# ROS_Car_F4VG_2024-01-24.net
KiCad netlist of a schematic drawn in EasyEDA Pro
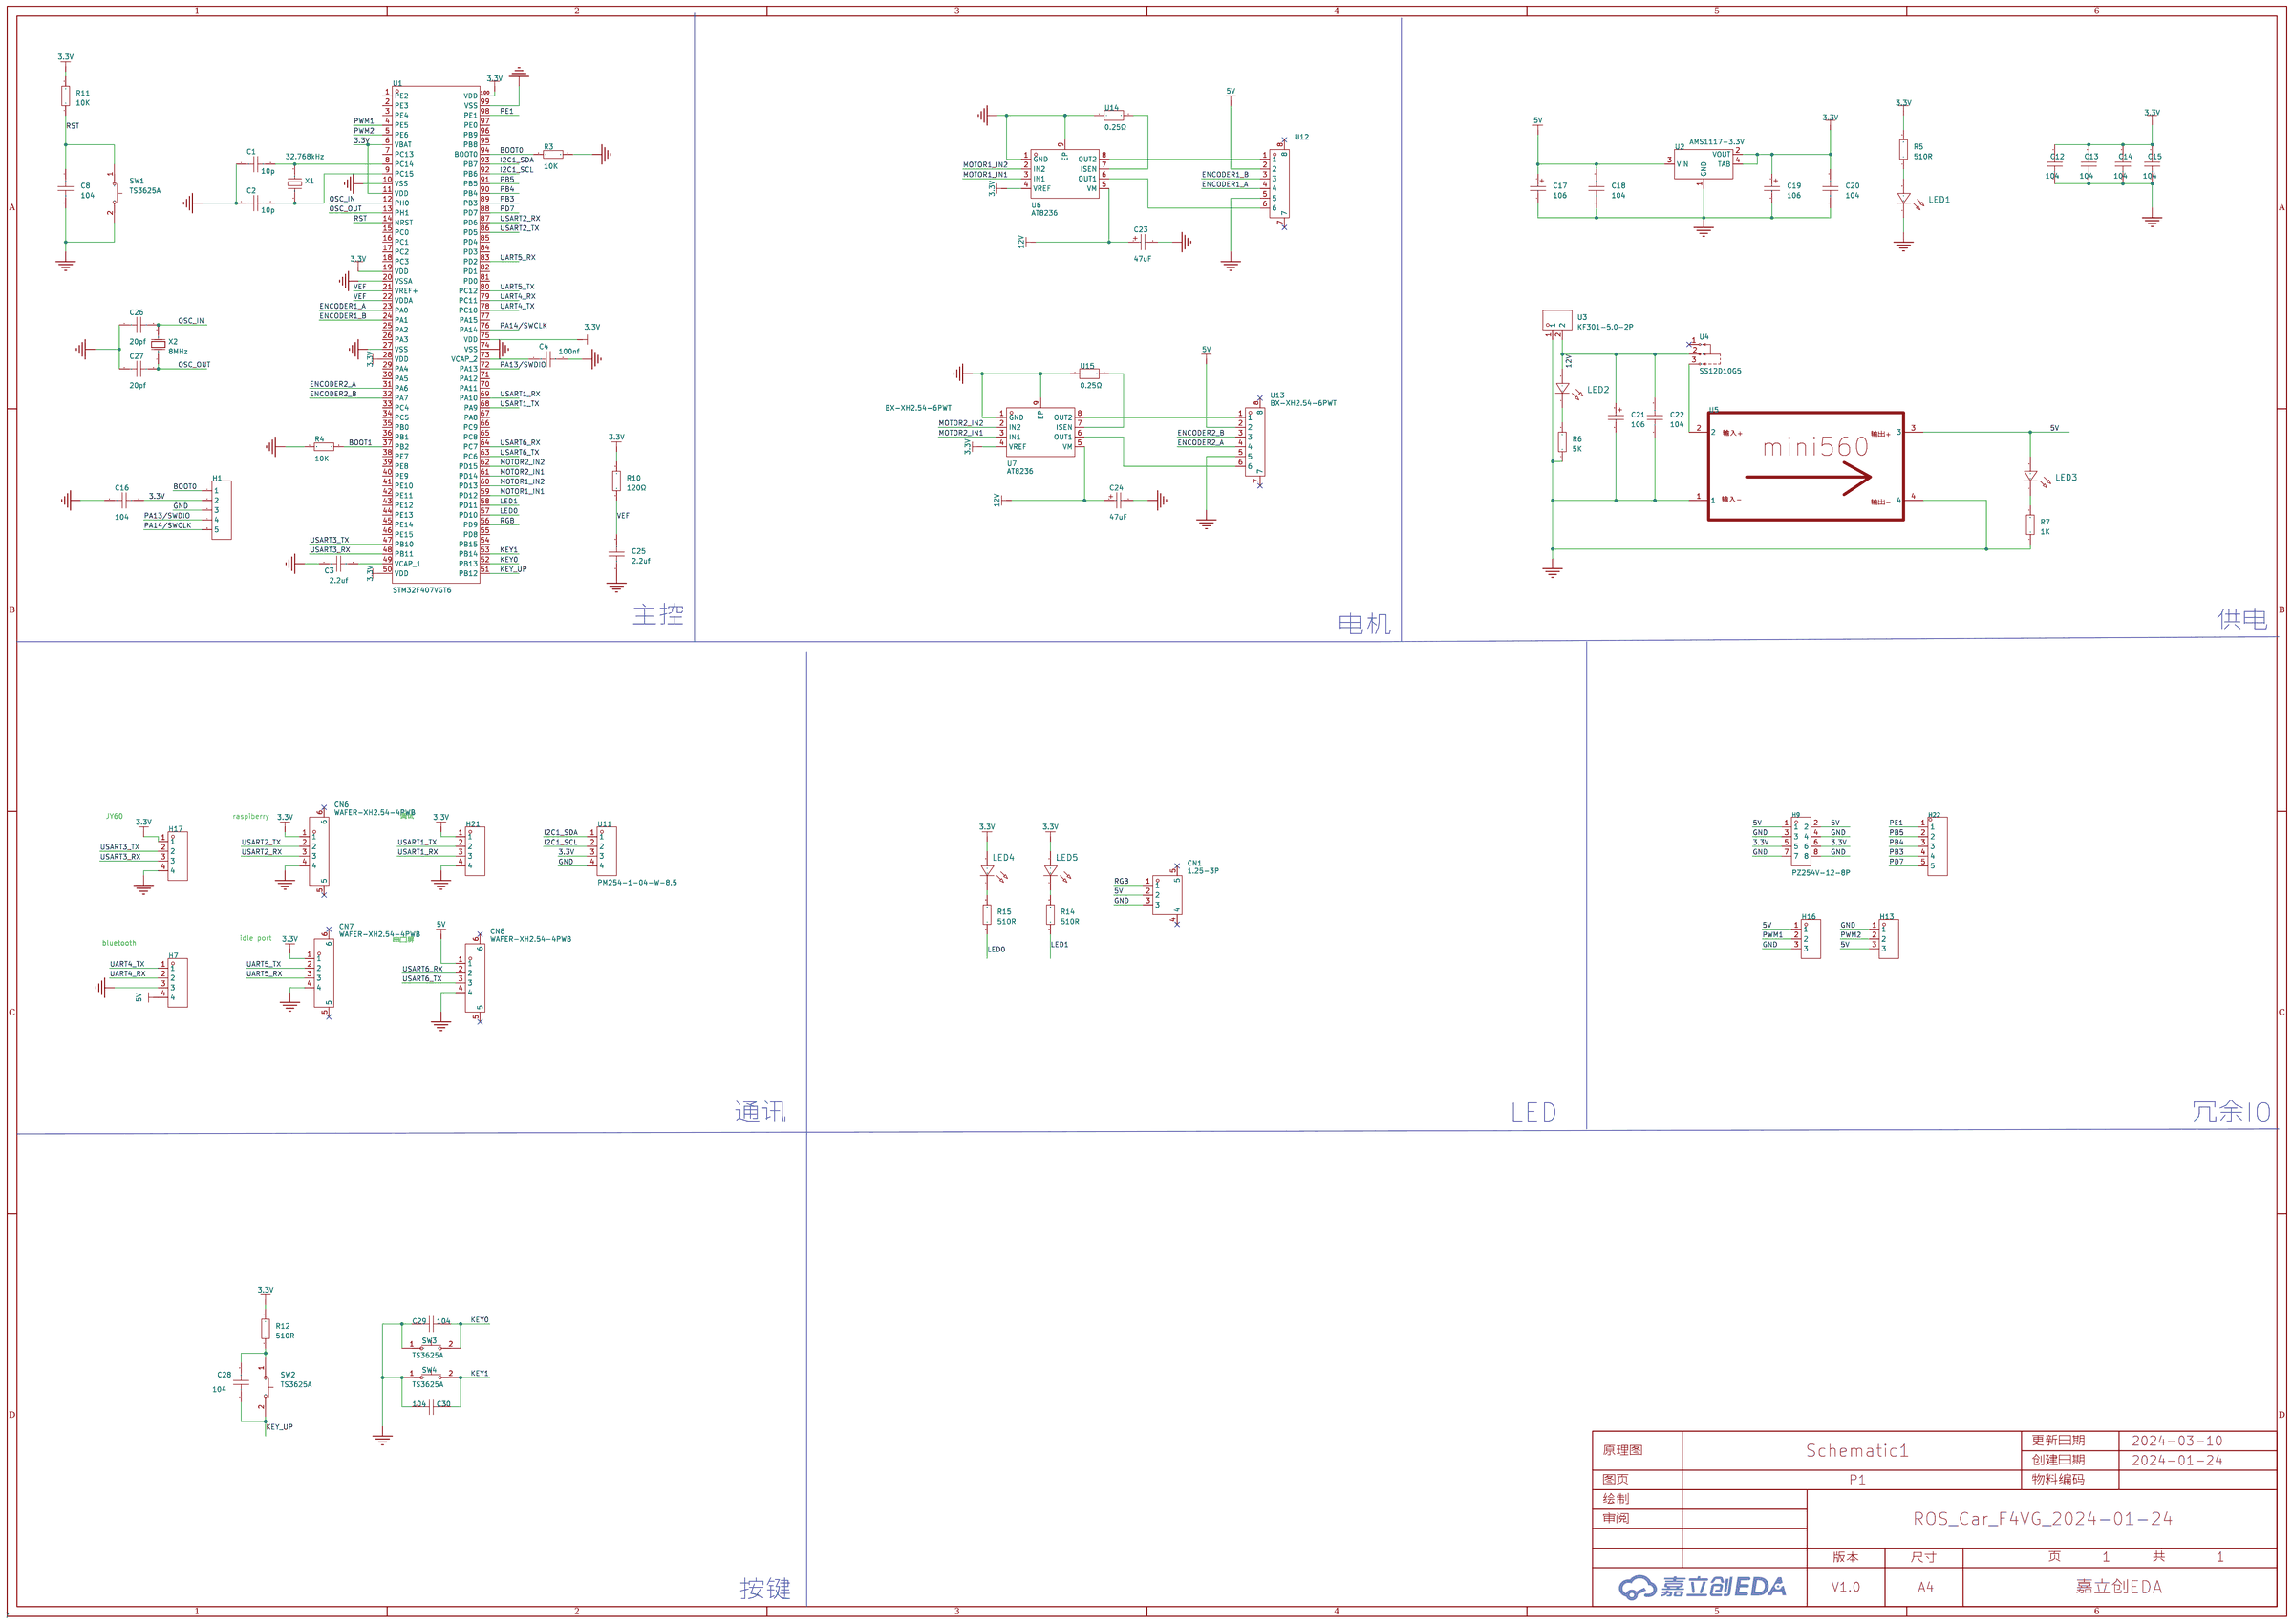
[diagram p0: schematic sheet]

(export (version "E")
  (design (tool "Eeschema 10.0.6"))
  (components
    (comp (ref "C1")
      (value "10p")
      (footprint "easyedapro:C0603")
      (libsource (lib "easyedapro") (part "CapAcitance"))
    )
    (comp (ref "C2")
      (value "10p")
      (footprint "easyedapro:C0603")
      (libsource (lib "easyedapro") (part "CapAcitance"))
    )
    (comp (ref "C3")
      (value "2.2uf")
      (footprint "easyedapro:C0603")
      (libsource (lib "easyedapro") (part "CapAcitance"))
    )
    (comp (ref "C4")
      (value "100nf")
      (footprint "easyedapro:C0603")
      (libsource (lib "easyedapro") (part "CapAcitance"))
    )
    (comp (ref "C8")
      (value "104")
      (footprint "easyedapro:C0603")
      (libsource (lib "easyedapro") (part "CapAcitance"))
    )
    (comp (ref "C12")
      (value "104")
      (footprint "easyedapro:C0603")
      (libsource (lib "easyedapro") (part "CapAcitance"))
    )
    (comp (ref "C13")
      (value "104")
      (footprint "easyedapro:C0603")
      (libsource (lib "easyedapro") (part "CapAcitance"))
    )
    (comp (ref "C14")
      (value "104")
      (footprint "easyedapro:C0603")
      (libsource (lib "easyedapro") (part "CapAcitance"))
    )
    (comp (ref "C15")
      (value "104")
      (footprint "easyedapro:C0603")
      (libsource (lib "easyedapro") (part "CapAcitance"))
    )
    (comp (ref "C16")
      (value "104")
      (footprint "easyedapro:C0603")
      (libsource (lib "easyedapro") (part "CapAcitance"))
    )
    (comp (ref "C17")
      (value "106")
      (footprint "easyedapro:C_Ele_SMD_4x5.5mm")
      (libsource (lib "easyedapro") (part "CAP"))
    )
    (comp (ref "C18")
      (value "104")
      (footprint "easyedapro:C0603")
      (libsource (lib "easyedapro") (part "CapAcitance"))
    )
    (comp (ref "C19")
      (value "106")
      (footprint "easyedapro:C_Ele_SMD_4x5.5mm")
      (libsource (lib "easyedapro") (part "CAP"))
    )
    (comp (ref "C20")
      (value "104")
      (footprint "easyedapro:C0603")
      (libsource (lib "easyedapro") (part "CapAcitance"))
    )
    (comp (ref "C21")
      (value "106")
      (footprint "easyedapro:C_Ele_SMD_4x5.5mm")
      (libsource (lib "easyedapro") (part "CAP"))
    )
    (comp (ref "C22")
      (value "104")
      (footprint "easyedapro:C0603")
      (libsource (lib "easyedapro") (part "CapAcitance"))
    )
    (comp (ref "C23")
      (value "47uF")
      (footprint "easyedapro:C_Ele_SMD_4x5.5mm")
      (libsource (lib "easyedapro") (part "CAP"))
    )
    (comp (ref "C24")
      (value "47uF")
      (footprint "easyedapro:C_Ele_SMD_4x5.5mm")
      (libsource (lib "easyedapro") (part "CAP"))
    )
    (comp (ref "C25")
      (value "2.2uf")
      (footprint "easyedapro:C0603")
      (libsource (lib "easyedapro") (part "CapAcitance"))
    )
    (comp (ref "C26")
      (value "20pf")
      (footprint "easyedapro:C0603")
      (libsource (lib "easyedapro") (part "CapAcitance"))
    )
    (comp (ref "C27")
      (value "20pf")
      (footprint "easyedapro:C0603")
      (libsource (lib "easyedapro") (part "CapAcitance"))
    )
    (comp (ref "C28")
      (value "104")
      (footprint "easyedapro:C0603")
      (libsource (lib "easyedapro") (part "CapAcitance"))
    )
    (comp (ref "C29")
      (value "104")
      (footprint "easyedapro:C0603")
      (libsource (lib "easyedapro") (part "CapAcitance"))
    )
    (comp (ref "C30")
      (value "104")
      (footprint "easyedapro:C0603")
      (libsource (lib "easyedapro") (part "CapAcitance"))
    )
    (comp (ref "CN1")
      (value "1.25-3P")
      (footprint "easyedapro:CONN-SMD_1.25-3P")
      (description "插针结构:1x3P;间距:1.25mm;安装方式:-;行距:-;总PIN数:3P;排数:1;每排PIN数:3;参考系列:-;触头材质:-;")
      (fields (field (name "Manufacturer") "SHOU HAN(首韩)"))
      (libsource (lib "easyedapro") (part "1.25-3P"))
    )
    (comp (ref "CN6")
      (value "WAFER-XH2.54-4PWB")
      (footprint "easyedapro:CONN-TH_4P-P0.20_XUNPU_WAFER-XH2.54-4PWB")
      (description "插针结构:1x4P;间距:2.5mm;安装方式:卧贴;总PIN数:4P;排数:1;每排PIN数:4;额定电流:3A;工作温度范围:-25°C~+85°C;")
      (fields (field (name "Manufacturer") "XUNPU(讯普)"))
      (libsource (lib "easyedapro") (part "WAFER-XH2.54-4PWB"))
    )
    (comp (ref "CN7")
      (value "WAFER-XH2.54-4PWB")
      (footprint "easyedapro:CONN-TH_4P-P0.20_XUNPU_WAFER-XH2.54-4PWB")
      (description "插针结构:1x4P;间距:2.5mm;安装方式:卧贴;总PIN数:4P;排数:1;每排PIN数:4;额定电流:3A;工作温度范围:-25°C~+85°C;")
      (fields (field (name "Manufacturer") "XUNPU(讯普)"))
      (libsource (lib "easyedapro") (part "WAFER-XH2.54-4PWB"))
    )
    (comp (ref "CN8")
      (value "WAFER-XH2.54-4PWB")
      (footprint "easyedapro:CONN-TH_4P-P0.20_XUNPU_WAFER-XH2.54-4PWB")
      (description "插针结构:1x4P;间距:2.5mm;安装方式:卧贴;总PIN数:4P;排数:1;每排PIN数:4;额定电流:3A;工作温度范围:-25°C~+85°C;")
      (fields (field (name "Manufacturer") "XUNPU(讯普)"))
      (libsource (lib "easyedapro") (part "WAFER-XH2.54-4PWB"))
    )
    (comp (ref "H1")
      (value "~")
      (footprint "easyedapro:HDR-TH_5P-P2.54-V-F")
      (libsource (lib "easyedapro") (part "Header-Female-2.54_1x5"))
    )
    (comp (ref "H7")
      (value "~")
      (footprint "easyedapro:HDR-TH_4P-P2.54-V-F")
      (libsource (lib "easyedapro") (part "2.54-1*4P母"))
    )
    (comp (ref "H9")
      (value "PZ254V-12-8P")
      (footprint "easyedapro:HDR-TH_8P-P2.54-V-M-R2-C4-S2.54")
      (fields (field (name "Manufacturer") "XFCN(兴飞)"))
      (libsource (lib "easyedapro") (part "PZ254V-12-8P"))
    )
    (comp (ref "H13")
      (value "~")
      (footprint "easyedapro:HDR-TH_3P-P2.54-V-F")
      (libsource (lib "easyedapro") (part "PM254V-11-03-H85"))
    )
    (comp (ref "H16")
      (value "~")
      (footprint "easyedapro:HDR-TH_3P-P2.54-V-M")
      (libsource (lib "easyedapro") (part "PZ254V-11-03P_C2937625"))
    )
    (comp (ref "H17")
      (value "~")
      (footprint "easyedapro:HDR-TH_4P-P2.54-V-F")
      (libsource (lib "easyedapro") (part "2.54-1*4P母"))
    )
    (comp (ref "H21")
      (value "~")
      (footprint "easyedapro:HDR-TH_4P-P2.54-V-M")
      (libsource (lib "easyedapro") (part "PZ254V-11-04P"))
    )
    (comp (ref "H22")
      (value "~")
      (footprint "easyedapro:HDR-TH_5P-P2.54-V-M")
      (libsource (lib "easyedapro") (part "MTP125-1105S1"))
    )
    (comp (ref "LED1")
      (value "~")
      (footprint "easyedapro:LED_0603")
      (libsource (lib "easyedapro") (part "LED_R"))
    )
    (comp (ref "LED2")
      (value "~")
      (footprint "easyedapro:LED_0603")
      (libsource (lib "easyedapro") (part "LED_R"))
    )
    (comp (ref "LED3")
      (value "~")
      (footprint "easyedapro:LED_0603")
      (libsource (lib "easyedapro") (part "LED_R"))
    )
    (comp (ref "LED4")
      (value "~")
      (footprint "easyedapro:LED_0603")
      (libsource (lib "easyedapro") (part "LED_R"))
    )
    (comp (ref "LED5")
      (value "~")
      (footprint "easyedapro:LED_0603")
      (libsource (lib "easyedapro") (part "LED_R"))
    )
    (comp (ref "R3") (value "10K") (footprint "easyedapro:R0603") (libsource (lib "easyedapro") (part "电阻")))
    (comp (ref "R4") (value "10K") (footprint "easyedapro:R0603") (libsource (lib "easyedapro") (part "电阻")))
    (comp (ref "R5") (value "510R") (footprint "easyedapro:R0603") (libsource (lib "easyedapro") (part "电阻")))
    (comp (ref "R6") (value "5K") (footprint "easyedapro:R0603") (libsource (lib "easyedapro") (part "电阻")))
    (comp (ref "R7") (value "1K") (footprint "easyedapro:R0603") (libsource (lib "easyedapro") (part "电阻")))
    (comp (ref "R10")
      (value "120Ω")
      (footprint "easyedapro:R0603")
      (libsource (lib "easyedapro") (part "电阻"))
    )
    (comp (ref "R11") (value "10K") (footprint "easyedapro:R0603") (libsource (lib "easyedapro") (part "电阻")))
    (comp (ref "R12")
      (value "510R")
      (footprint "easyedapro:R0603")
      (libsource (lib "easyedapro") (part "电阻"))
    )
    (comp (ref "R14")
      (value "510R")
      (footprint "easyedapro:R0603")
      (libsource (lib "easyedapro") (part "电阻"))
    )
    (comp (ref "R15")
      (value "510R")
      (footprint "easyedapro:R0603")
      (libsource (lib "easyedapro") (part "电阻"))
    )
    (comp (ref "SW1")
      (value "TS3625A")
      (footprint "easyedapro:KEY-SMD_L6.0-W3.5-LS8.4")
      (fields (field (name "Manufacturer") "SHOU HAN(首韩)"))
      (libsource (lib "easyedapro") (part "TS3625A"))
    )
    (comp (ref "SW2")
      (value "TS3625A")
      (footprint "easyedapro:KEY-SMD_L6.0-W3.5-LS8.4")
      (fields (field (name "Manufacturer") "SHOU HAN(首韩)"))
      (libsource (lib "easyedapro") (part "TS3625A"))
    )
    (comp (ref "SW3")
      (value "TS3625A")
      (footprint "easyedapro:KEY-SMD_L6.0-W3.5-LS8.4")
      (fields (field (name "Manufacturer") "SHOU HAN(首韩)"))
      (libsource (lib "easyedapro") (part "TS3625A"))
    )
    (comp (ref "SW4")
      (value "TS3625A")
      (footprint "easyedapro:KEY-SMD_L6.0-W3.5-LS8.4")
      (fields (field (name "Manufacturer") "SHOU HAN(首韩)"))
      (libsource (lib "easyedapro") (part "TS3625A"))
    )
    (comp (ref "U1")
      (value "STM32F407VGT6")
      (footprint "easyedapro:LQFP-100_L14.0-W14.0-P0.50-LS16.0-BL")
      (fields (field (name "Manufacturer") "ST(意法半导体)"))
      (libsource (lib "easyedapro") (part "STM32F407VGT6"))
    )
    (comp (ref "U2")
      (value "AMS1117-3.3V")
      (footprint "easyedapro:SOT_223")
      (libsource (lib "easyedapro") (part "AMS1117"))
    )
    (comp (ref "U3")
      (value "KF301-5.0-2P")
      (footprint "easyedapro:CONN-TH_P5.00_KF301-5.0-2P")
      (fields (field (name "Manufacturer") "KEFA(科发)"))
      (libsource (lib "easyedapro") (part "KF301-5.0-2P"))
    )
    (comp (ref "U4")
      (value "SS12D10G5")
      (footprint "easyedapro:SW-TH_SHOU-HAN_SS12D10G4")
      (fields (field (name "Manufacturer") "SHOU HAN(首韩)"))
      (libsource (lib "easyedapro") (part "SS12D10G5"))
    )
    (comp (ref "U5")
      (value "~")
      (footprint "easyedapro:min560邮票孔")
      (libsource (lib "easyedapro") (part "mini560邮票孔"))
    )
    (comp (ref "U6")
      (value "AT8236")
      (footprint "easyedapro:ESOP-8_L4.9-W3.9-P1.27-LS6.0-BL-EP")
      (fields (field (name "Manufacturer") "杭州中科微"))
      (libsource (lib "easyedapro") (part "AT8236"))
    )
    (comp (ref "U7")
      (value "AT8236")
      (footprint "easyedapro:ESOP-8_L4.9-W3.9-P1.27-LS6.0-BL-EP")
      (fields (field (name "Manufacturer") "杭州中科微"))
      (libsource (lib "easyedapro") (part "AT8236"))
    )
    (comp (ref "U11")
      (value "PM254-1-04-W-8.5")
      (footprint "easyedapro:HDR-TH_4P-P2.54-H-F-W10.0-N")
      (fields (field (name "Manufacturer") "HCTL(华灿天禄)"))
      (libsource (lib "easyedapro") (part "PM254-1-04-W-8.5"))
    )
    (comp (ref "U12")
      (value "BX-XH2.54-6PWT")
      (footprint "easyedapro:CONN-SMD_6P-P2.50_BX-XH2.54-6PWT")
      (fields (field (name "Manufacturer") "Bossie(博锡)"))
      (libsource (lib "easyedapro") (part "BX-XH2.54-6PWT"))
    )
    (comp (ref "U13")
      (value "BX-XH2.54-6PWT")
      (footprint "easyedapro:CONN-SMD_6P-P2.50_BX-XH2.54-6PWT")
      (fields (field (name "Manufacturer") "Bossie(博锡)"))
      (libsource (lib "easyedapro") (part "BX-XH2.54-6PWT"))
    )
    (comp (ref "U14")
      (value "0.25Ω")
      (footprint "easyedapro:R2512")
      (description "阻值:1Ω;精度:±1%;")
      (fields (field (name "Manufacturer Part") "SCR2512F1R") (field (name "Manufacturer") "VO(翔胜)"))
      (libsource (lib "easyedapro") (part "SCR2512F1R"))
    )
    (comp (ref "U15")
      (value "0.25Ω")
      (footprint "easyedapro:R2512")
      (description "阻值:1Ω;精度:±1%;")
      (fields (field (name "Manufacturer Part") "SCR2512F1R") (field (name "Manufacturer") "VO(翔胜)"))
      (libsource (lib "easyedapro") (part "SCR2512F1R"))
    )
    (comp (ref "X1")
      (value "32.768kHz")
      (footprint "easyedapro:OSC-SMD_L3.2-W1.5")
      (description "晶振类型:贴片晶振;频率:32.768kHz;常温频差:±20ppm;外接负载电容:12.5pF;")
      (fields (field (name "Manufacturer Part") "X321532768KGD2SI") (field (name "Manufacturer") "YXC(扬兴晶振)"))
      (libsource (lib "easyedapro") (part "X321532768KGD2SI"))
    )
    (comp (ref "X2")
      (value "8MHz")
      (footprint "easyedapro:CRYSTAL-SMD_L5.0-W3.2")
      (description "晶振类型:贴片晶振;频率:8MHz;常温频差:±10ppm;外接负载电容:20pF;频率稳定度(全温):±50ppm;")
      (fields (field (name "Manufacturer Part") "X50328MSB2GI") (field (name "Manufacturer") "YXC(扬兴晶振)"))
      (libsource (lib "easyedapro") (part "X50328MSB2GI"))
    )
  )
  (nets
    (net (code "1") (name "/BOOT0") (class "Default")
      (node (ref "H1") (pin "1") (pinfunction "1_1") (pintype "input"))
      (node (ref "R3") (pin "1") (pinfunction "1_1") (pintype "input"))
      (node (ref "U1") (pin "94") (pinfunction "BOOT0_94") (pintype "unspecified"))
    )
    (net (code "2") (name "/BOOT1") (class "Default")
      (node (ref "R4") (pin "2") (pinfunction "2_2") (pintype "input"))
      (node (ref "U1") (pin "37") (pinfunction "PB2_37") (pintype "unspecified"))
    )
    (net (code "3") (name "/ENCODER1_A") (class "Default")
      (node (ref "U1") (pin "23") (pinfunction "PA0_23") (pintype "unspecified"))
      (node (ref "U12") (pin "4") (pinfunction "4_4") (pintype "unspecified"))
    )
    (net (code "4") (name "/ENCODER1_B") (class "Default")
      (node (ref "U1") (pin "24") (pinfunction "PA1_24") (pintype "unspecified"))
      (node (ref "U12") (pin "3") (pinfunction "3_3") (pintype "unspecified"))
    )
    (net (code "5") (name "/ENCODER2_A") (class "Default")
      (node (ref "U1") (pin "31") (pinfunction "PA6_31") (pintype "unspecified"))
      (node (ref "U13") (pin "4") (pinfunction "4_4") (pintype "unspecified"))
    )
    (net (code "6") (name "/ENCODER2_B") (class "Default")
      (node (ref "U1") (pin "32") (pinfunction "PA7_32") (pintype "unspecified"))
      (node (ref "U13") (pin "3") (pinfunction "3_3") (pintype "unspecified"))
    )
    (net (code "7") (name "/I2C1_SCL") (class "Default")
      (node (ref "U1") (pin "92") (pinfunction "PB6_92") (pintype "unspecified"))
      (node (ref "U11") (pin "2") (pinfunction "2_2") (pintype "unspecified"))
    )
    (net (code "8") (name "/I2C1_SDA") (class "Default")
      (node (ref "U1") (pin "93") (pinfunction "PB7_93") (pintype "unspecified"))
      (node (ref "U11") (pin "1") (pinfunction "1_1") (pintype "unspecified"))
    )
    (net (code "9") (name "/KEY0") (class "Default")
      (node (ref "C29") (pin "1") (pinfunction "1_1") (pintype "input"))
      (node (ref "SW3") (pin "2") (pinfunction "2_2") (pintype "unspecified"))
      (node (ref "U1") (pin "52") (pinfunction "PB13_52") (pintype "unspecified"))
    )
    (net (code "10") (name "/KEY1") (class "Default")
      (node (ref "C30") (pin "1") (pinfunction "1_1") (pintype "input"))
      (node (ref "SW4") (pin "2") (pinfunction "2_2") (pintype "unspecified"))
      (node (ref "U1") (pin "53") (pinfunction "PB14_53") (pintype "unspecified"))
    )
    (net (code "11") (name "/KEY_UP") (class "Default")
      (node (ref "C28") (pin "1") (pinfunction "1_1") (pintype "input"))
      (node (ref "SW2") (pin "2") (pinfunction "2_2") (pintype "unspecified"))
      (node (ref "U1") (pin "51") (pinfunction "PB12_51") (pintype "unspecified"))
    )
    (net (code "12") (name "/LED0") (class "Default")
      (node (ref "R15") (pin "1") (pinfunction "1_1") (pintype "input"))
      (node (ref "U1") (pin "57") (pinfunction "PD10_57") (pintype "unspecified"))
    )
    (net (code "13") (name "/LED1") (class "Default")
      (node (ref "R14") (pin "1") (pinfunction "1_1") (pintype "input"))
      (node (ref "U1") (pin "58") (pinfunction "PD11_58") (pintype "unspecified"))
    )
    (net (code "14") (name "/MOTOR1_IN1") (class "Default")
      (node (ref "U1") (pin "59") (pinfunction "PD12_59") (pintype "unspecified"))
      (node (ref "U6") (pin "3") (pinfunction "IN1_3") (pintype "unspecified"))
    )
    (net (code "15") (name "/MOTOR1_IN2") (class "Default")
      (node (ref "U1") (pin "60") (pinfunction "PD13_60") (pintype "unspecified"))
      (node (ref "U6") (pin "2") (pinfunction "IN2_2") (pintype "unspecified"))
    )
    (net (code "16") (name "/MOTOR2_IN1") (class "Default")
      (node (ref "U1") (pin "61") (pinfunction "PD14_61") (pintype "unspecified"))
      (node (ref "U7") (pin "3") (pinfunction "IN1_3") (pintype "unspecified"))
    )
    (net (code "17") (name "/MOTOR2_IN2") (class "Default")
      (node (ref "U1") (pin "62") (pinfunction "PD15_62") (pintype "unspecified"))
      (node (ref "U7") (pin "2") (pinfunction "IN2_2") (pintype "unspecified"))
    )
    (net (code "18") (name "/OSC_IN") (class "Default")
      (node (ref "C26") (pin "2") (pinfunction "2_2") (pintype "input"))
      (node (ref "U1") (pin "12") (pinfunction "PH0_12") (pintype "unspecified"))
      (node (ref "X2") (pin "2") (pinfunction "OSC2_2") (pintype "input"))
    )
    (net (code "19") (name "/OSC_OUT") (class "Default")
      (node (ref "C27") (pin "2") (pinfunction "2_2") (pintype "input"))
      (node (ref "U1") (pin "13") (pinfunction "PH1_13") (pintype "unspecified"))
      (node (ref "X2") (pin "1") (pinfunction "OSC1_1") (pintype "input"))
    )
    (net (code "20") (name "/PA13{slash}SWDIO") (class "Default")
      (node (ref "H1") (pin "4") (pinfunction "4_4") (pintype "input"))
      (node (ref "U1") (pin "72") (pinfunction "PA13_72") (pintype "unspecified"))
    )
    (net (code "21") (name "/PA14{slash}SWCLK") (class "Default")
      (node (ref "H1") (pin "5") (pinfunction "5_5") (pintype "input"))
      (node (ref "U1") (pin "76") (pinfunction "PA14_76") (pintype "unspecified"))
    )
    (net (code "22") (name "/PB3") (class "Default")
      (node (ref "H22") (pin "4") (pinfunction "4_4") (pintype "input"))
      (node (ref "U1") (pin "89") (pinfunction "PB3_89") (pintype "unspecified"))
    )
    (net (code "23") (name "/PB4") (class "Default")
      (node (ref "H22") (pin "3") (pinfunction "3_3") (pintype "input"))
      (node (ref "U1") (pin "90") (pinfunction "PB4_90") (pintype "unspecified"))
    )
    (net (code "24") (name "/PB5") (class "Default")
      (node (ref "H22") (pin "2") (pinfunction "2_2") (pintype "input"))
      (node (ref "U1") (pin "91") (pinfunction "PB5_91") (pintype "unspecified"))
    )
    (net (code "25") (name "/PD7") (class "Default")
      (node (ref "H22") (pin "5") (pinfunction "5_5") (pintype "input"))
      (node (ref "U1") (pin "88") (pinfunction "PD7_88") (pintype "unspecified"))
    )
    (net (code "26") (name "/PE1") (class "Default")
      (node (ref "H22") (pin "1") (pinfunction "1_1") (pintype "input"))
      (node (ref "U1") (pin "98") (pinfunction "PE1_98") (pintype "unspecified"))
    )
    (net (code "27") (name "/PWM1") (class "Default")
      (node (ref "H16") (pin "2") (pinfunction "2_2") (pintype "input"))
      (node (ref "U1") (pin "4") (pinfunction "PE5_4") (pintype "unspecified"))
    )
    (net (code "28") (name "/PWM2") (class "Default")
      (node (ref "H13") (pin "2") (pinfunction "2_2") (pintype "unspecified"))
      (node (ref "U1") (pin "5") (pinfunction "PE6_5") (pintype "unspecified"))
    )
    (net (code "29") (name "/RGB") (class "Default")
      (node (ref "CN1") (pin "1") (pinfunction "1_1") (pintype "unspecified"))
      (node (ref "U1") (pin "56") (pinfunction "PD9_56") (pintype "unspecified"))
    )
    (net (code "30") (name "/RST") (class "Default")
      (node (ref "C8") (pin "1") (pinfunction "1_1") (pintype "input"))
      (node (ref "R11") (pin "1") (pinfunction "1_1") (pintype "input"))
      (node (ref "SW1") (pin "1") (pinfunction "1_1") (pintype "unspecified"))
      (node (ref "U1") (pin "14") (pinfunction "NRST_14") (pintype "unspecified"))
    )
    (net (code "31") (name "/UART4_RX") (class "Default")
      (node (ref "H7") (pin "2") (pinfunction "2_2") (pintype "unspecified"))
      (node (ref "U1") (pin "79") (pinfunction "PC11_79") (pintype "unspecified"))
    )
    (net (code "32") (name "/UART4_TX") (class "Default")
      (node (ref "H7") (pin "1") (pinfunction "1_1") (pintype "unspecified"))
      (node (ref "U1") (pin "78") (pinfunction "PC10_78") (pintype "unspecified"))
    )
    (net (code "33") (name "/UART5_RX") (class "Default")
      (node (ref "CN7") (pin "3") (pinfunction "3_3") (pintype "unspecified"))
      (node (ref "U1") (pin "83") (pinfunction "PD2_83") (pintype "unspecified"))
    )
    (net (code "34") (name "/UART5_TX") (class "Default")
      (node (ref "CN7") (pin "2") (pinfunction "2_2") (pintype "unspecified"))
      (node (ref "U1") (pin "80") (pinfunction "PC12_80") (pintype "unspecified"))
    )
    (net (code "35") (name "/USART1_RX") (class "Default")
      (node (ref "H21") (pin "3") (pinfunction "3_3") (pintype "unspecified"))
      (node (ref "U1") (pin "69") (pinfunction "PA10_69") (pintype "unspecified"))
    )
    (net (code "36") (name "/USART1_TX") (class "Default")
      (node (ref "H21") (pin "2") (pinfunction "2_2") (pintype "unspecified"))
      (node (ref "U1") (pin "68") (pinfunction "PA9_68") (pintype "unspecified"))
    )
    (net (code "37") (name "/USART2_RX") (class "Default")
      (node (ref "CN6") (pin "3") (pinfunction "3_3") (pintype "unspecified"))
      (node (ref "U1") (pin "87") (pinfunction "PD6_87") (pintype "unspecified"))
    )
    (net (code "38") (name "/USART2_TX") (class "Default")
      (node (ref "CN6") (pin "2") (pinfunction "2_2") (pintype "unspecified"))
      (node (ref "U1") (pin "86") (pinfunction "PD5_86") (pintype "unspecified"))
    )
    (net (code "39") (name "/USART3_RX") (class "Default")
      (node (ref "H17") (pin "3") (pinfunction "3_3") (pintype "unspecified"))
      (node (ref "U1") (pin "48") (pinfunction "PB11_48") (pintype "unspecified"))
    )
    (net (code "40") (name "/USART3_TX") (class "Default")
      (node (ref "H17") (pin "2") (pinfunction "2_2") (pintype "unspecified"))
      (node (ref "U1") (pin "47") (pinfunction "PB10_47") (pintype "unspecified"))
    )
    (net (code "41") (name "/USART6_RX") (class "Default")
      (node (ref "CN8") (pin "2") (pinfunction "2_2") (pintype "unspecified"))
      (node (ref "U1") (pin "64") (pinfunction "PC7_64") (pintype "unspecified"))
    )
    (net (code "42") (name "/USART6_TX") (class "Default")
      (node (ref "CN8") (pin "3") (pinfunction "3_3") (pintype "unspecified"))
      (node (ref "U1") (pin "63") (pinfunction "PC6_63") (pintype "unspecified"))
    )
    (net (code "43") (name "/VEF") (class "Default")
      (node (ref "C25") (pin "2") (pinfunction "2_2") (pintype "input"))
      (node (ref "R10") (pin "1") (pinfunction "1_1") (pintype "input"))
      (node (ref "U1") (pin "21") (pinfunction "VREF+_21") (pintype "unspecified"))
      (node (ref "U1") (pin "22") (pinfunction "VDDA_22") (pintype "unspecified"))
    )
    (net (code "44") (name "3.3V") (class "Default")
      (node (ref "C12") (pin "2") (pinfunction "2_2") (pintype "input"))
      (node (ref "C13") (pin "2") (pinfunction "2_2") (pintype "input"))
      (node (ref "C14") (pin "2") (pinfunction "2_2") (pintype "input"))
      (node (ref "C15") (pin "2") (pinfunction "2_2") (pintype "input"))
      (node (ref "C16") (pin "2") (pinfunction "2_2") (pintype "input"))
      (node (ref "C19") (pin "1") (pinfunction "1_1") (pintype "input"))
      (node (ref "C20") (pin "2") (pinfunction "2_2") (pintype "input"))
      (node (ref "CN6") (pin "1") (pinfunction "1_1") (pintype "unspecified"))
      (node (ref "CN7") (pin "1") (pinfunction "1_1") (pintype "unspecified"))
      (node (ref "H1") (pin "2") (pinfunction "2_2") (pintype "input"))
      (node (ref "H17") (pin "1") (pinfunction "1_1") (pintype "unspecified"))
      (node (ref "H21") (pin "1") (pinfunction "1_1") (pintype "unspecified"))
      (node (ref "H9") (pin "5") (pinfunction "5_5") (pintype "input"))
      (node (ref "H9") (pin "6") (pinfunction "6_6") (pintype "input"))
      (node (ref "LED4") (pin "2") (pinfunction "A_2") (pintype "input"))
      (node (ref "LED5") (pin "2") (pinfunction "A_2") (pintype "input"))
      (node (ref "R10") (pin "2") (pinfunction "2_2") (pintype "input"))
      (node (ref "R11") (pin "2") (pinfunction "2_2") (pintype "input"))
      (node (ref "R12") (pin "1") (pinfunction "1_1") (pintype "input"))
      (node (ref "R5") (pin "2") (pinfunction "2_2") (pintype "input"))
      (node (ref "U1") (pin "100") (pinfunction "VDD_100") (pintype "unspecified"))
      (node (ref "U1") (pin "11") (pinfunction "VDD_11") (pintype "unspecified"))
      (node (ref "U1") (pin "19") (pinfunction "VDD_19") (pintype "unspecified"))
      (node (ref "U1") (pin "28") (pinfunction "VDD_28") (pintype "unspecified"))
      (node (ref "U1") (pin "50") (pinfunction "VDD_50") (pintype "unspecified"))
      (node (ref "U1") (pin "6") (pinfunction "VBAT_6") (pintype "unspecified"))
      (node (ref "U1") (pin "75") (pinfunction "VDD_75") (pintype "unspecified"))
      (node (ref "U11") (pin "3") (pinfunction "3_3") (pintype "unspecified"))
      (node (ref "U2") (pin "2") (pinfunction "VOUT_2") (pintype "input"))
      (node (ref "U2") (pin "4") (pinfunction "TAB_4") (pintype "input"))
      (node (ref "U6") (pin "4") (pinfunction "VREF_4") (pintype "unspecified"))
      (node (ref "U7") (pin "4") (pinfunction "VREF_4") (pintype "unspecified"))
    )
    (net (code "45") (name "5V") (class "Default")
      (node (ref "C17") (pin "1") (pinfunction "1_1") (pintype "input"))
      (node (ref "C18") (pin "2") (pinfunction "2_2") (pintype "input"))
      (node (ref "CN1") (pin "2") (pinfunction "2_2") (pintype "unspecified"))
      (node (ref "CN8") (pin "1") (pinfunction "1_1") (pintype "unspecified"))
      (node (ref "H13") (pin "3") (pinfunction "3_3") (pintype "unspecified"))
      (node (ref "H16") (pin "1") (pinfunction "1_1") (pintype "input"))
      (node (ref "H7") (pin "4") (pinfunction "4_4") (pintype "unspecified"))
      (node (ref "H9") (pin "1") (pinfunction "1_1") (pintype "input"))
      (node (ref "H9") (pin "2") (pinfunction "2_2") (pintype "input"))
      (node (ref "LED3") (pin "2") (pinfunction "A_2") (pintype "input"))
      (node (ref "U12") (pin "2") (pinfunction "2_2") (pintype "unspecified"))
      (node (ref "U13") (pin "2") (pinfunction "2_2") (pintype "unspecified"))
      (node (ref "U2") (pin "3") (pinfunction "VIN_3") (pintype "input"))
      (node (ref "U5") (pin "3") (pinfunction "3_3") (pintype "input"))
    )
    (net (code "46") (name "12V") (class "Default")
      (node (ref "C21") (pin "1") (pinfunction "1_1") (pintype "input"))
      (node (ref "C22") (pin "2") (pinfunction "2_2") (pintype "input"))
      (node (ref "C23") (pin "1") (pinfunction "1_1") (pintype "input"))
      (node (ref "C24") (pin "1") (pinfunction "1_1") (pintype "input"))
      (node (ref "LED2") (pin "2") (pinfunction "A_2") (pintype "input"))
      (node (ref "U3") (pin "2") (pinfunction "2_2") (pintype "unspecified"))
      (node (ref "U4") (pin "2") (pinfunction "2_2") (pintype "unspecified"))
      (node (ref "U6") (pin "5") (pinfunction "VM_5") (pintype "unspecified"))
      (node (ref "U7") (pin "5") (pinfunction "VM_5") (pintype "unspecified"))
    )
    (net (code "47") (name "GND") (class "Default")
      (node (ref "C1") (pin "1") (pinfunction "1_1") (pintype "input"))
      (node (ref "C12") (pin "1") (pinfunction "1_1") (pintype "input"))
      (node (ref "C13") (pin "1") (pinfunction "1_1") (pintype "input"))
      (node (ref "C14") (pin "1") (pinfunction "1_1") (pintype "input"))
      (node (ref "C15") (pin "1") (pinfunction "1_1") (pintype "input"))
      (node (ref "C16") (pin "1") (pinfunction "1_1") (pintype "input"))
      (node (ref "C17") (pin "2") (pinfunction "2_2") (pintype "input"))
      (node (ref "C18") (pin "1") (pinfunction "1_1") (pintype "input"))
      (node (ref "C19") (pin "2") (pinfunction "2_2") (pintype "input"))
      (node (ref "C2") (pin "1") (pinfunction "1_1") (pintype "input"))
      (node (ref "C20") (pin "1") (pinfunction "1_1") (pintype "input"))
      (node (ref "C21") (pin "2") (pinfunction "2_2") (pintype "input"))
      (node (ref "C22") (pin "1") (pinfunction "1_1") (pintype "input"))
      (node (ref "C23") (pin "2") (pinfunction "2_2") (pintype "input"))
      (node (ref "C24") (pin "2") (pinfunction "2_2") (pintype "input"))
      (node (ref "C25") (pin "1") (pinfunction "1_1") (pintype "input"))
      (node (ref "C26") (pin "1") (pinfunction "1_1") (pintype "input"))
      (node (ref "C27") (pin "1") (pinfunction "1_1") (pintype "input"))
      (node (ref "C29") (pin "2") (pinfunction "2_2") (pintype "input"))
      (node (ref "C3") (pin "1") (pinfunction "1_1") (pintype "input"))
      (node (ref "C30") (pin "2") (pinfunction "2_2") (pintype "input"))
      (node (ref "C4") (pin "2") (pinfunction "2_2") (pintype "input"))
      (node (ref "C8") (pin "2") (pinfunction "2_2") (pintype "input"))
      (node (ref "CN1") (pin "3") (pinfunction "3_3") (pintype "unspecified"))
      (node (ref "CN6") (pin "4") (pinfunction "4_4") (pintype "unspecified"))
      (node (ref "CN7") (pin "4") (pinfunction "4_4") (pintype "unspecified"))
      (node (ref "CN8") (pin "4") (pinfunction "4_4") (pintype "unspecified"))
      (node (ref "H1") (pin "3") (pinfunction "3_3") (pintype "input"))
      (node (ref "H13") (pin "1") (pinfunction "1_1") (pintype "unspecified"))
      (node (ref "H16") (pin "3") (pinfunction "3_3") (pintype "input"))
      (node (ref "H17") (pin "4") (pinfunction "4_4") (pintype "unspecified"))
      (node (ref "H21") (pin "4") (pinfunction "4_4") (pintype "unspecified"))
      (node (ref "H7") (pin "3") (pinfunction "3_3") (pintype "unspecified"))
      (node (ref "H9") (pin "3") (pinfunction "3_3") (pintype "input"))
      (node (ref "H9") (pin "4") (pinfunction "4_4") (pintype "input"))
      (node (ref "H9") (pin "7") (pinfunction "7_7") (pintype "input"))
      (node (ref "H9") (pin "8") (pinfunction "8_8") (pintype "input"))
      (node (ref "LED1") (pin "1") (pinfunction "C_1") (pintype "input"))
      (node (ref "R3") (pin "2") (pinfunction "2_2") (pintype "input"))
      (node (ref "R4") (pin "1") (pinfunction "1_1") (pintype "input"))
      (node (ref "R6") (pin "1") (pinfunction "1_1") (pintype "input"))
      (node (ref "R7") (pin "1") (pinfunction "1_1") (pintype "input"))
      (node (ref "SW1") (pin "2") (pinfunction "2_2") (pintype "unspecified"))
      (node (ref "SW3") (pin "1") (pinfunction "1_1") (pintype "unspecified"))
      (node (ref "SW4") (pin "1") (pinfunction "1_1") (pintype "unspecified"))
      (node (ref "U1") (pin "10") (pinfunction "VSS_10") (pintype "unspecified"))
      (node (ref "U1") (pin "20") (pinfunction "VSSA_20") (pintype "unspecified"))
      (node (ref "U1") (pin "27") (pinfunction "VSS_27") (pintype "unspecified"))
      (node (ref "U1") (pin "74") (pinfunction "VSS_74") (pintype "unspecified"))
      (node (ref "U1") (pin "99") (pinfunction "VSS_99") (pintype "unspecified"))
      (node (ref "U11") (pin "4") (pinfunction "4_4") (pintype "unspecified"))
      (node (ref "U12") (pin "5") (pinfunction "5_5") (pintype "unspecified"))
      (node (ref "U13") (pin "5") (pinfunction "5_5") (pintype "unspecified"))
      (node (ref "U14") (pin "1") (pinfunction "1_1") (pintype "input"))
      (node (ref "U15") (pin "1") (pinfunction "1_1") (pintype "input"))
      (node (ref "U2") (pin "1") (pinfunction "GND_1") (pintype "input"))
      (node (ref "U3") (pin "1") (pinfunction "1_1") (pintype "unspecified"))
      (node (ref "U5") (pin "1") (pinfunction "1_1") (pintype "input"))
      (node (ref "U5") (pin "4") (pinfunction "4_4") (pintype "input"))
      (node (ref "U6") (pin "1") (pinfunction "GND_1") (pintype "unspecified"))
      (node (ref "U6") (pin "9") (pinfunction "EP_9") (pintype "unspecified"))
      (node (ref "U7") (pin "1") (pinfunction "GND_1") (pintype "unspecified"))
      (node (ref "U7") (pin "9") (pinfunction "EP_9") (pintype "unspecified"))
    )
    (net (code "48") (name "Net-(C28-Pad2)") (class "Default")
      (node (ref "C28") (pin "2") (pinfunction "2_2") (pintype "input"))
      (node (ref "R12") (pin "2") (pinfunction "2_2") (pintype "input"))
      (node (ref "SW2") (pin "1") (pinfunction "1_1") (pintype "unspecified"))
    )
    (net (code "49") (name "Net-(LED1-A)") (class "Default")
      (node (ref "LED1") (pin "2") (pinfunction "A_2") (pintype "input"))
      (node (ref "R5") (pin "1") (pinfunction "1_1") (pintype "input"))
    )
    (net (code "50") (name "Net-(LED2-C)") (class "Default")
      (node (ref "LED2") (pin "1") (pinfunction "C_1") (pintype "input"))
      (node (ref "R6") (pin "2") (pinfunction "2_2") (pintype "input"))
    )
    (net (code "51") (name "Net-(LED3-C)") (class "Default")
      (node (ref "LED3") (pin "1") (pinfunction "C_1") (pintype "input"))
      (node (ref "R7") (pin "2") (pinfunction "2_2") (pintype "input"))
    )
    (net (code "52") (name "Net-(LED4-C)") (class "Default")
      (node (ref "LED4") (pin "1") (pinfunction "C_1") (pintype "input"))
      (node (ref "R15") (pin "2") (pinfunction "2_2") (pintype "input"))
    )
    (net (code "53") (name "Net-(LED5-C)") (class "Default")
      (node (ref "LED5") (pin "1") (pinfunction "C_1") (pintype "input"))
      (node (ref "R14") (pin "2") (pinfunction "2_2") (pintype "input"))
    )
    (net (code "54") (name "Net-(U1-PC14)") (class "Default")
      (node (ref "C1") (pin "2") (pinfunction "2_2") (pintype "input"))
      (node (ref "U1") (pin "8") (pinfunction "PC14_8") (pintype "unspecified"))
      (node (ref "X1") (pin "2") (pinfunction "2_2") (pintype "input"))
    )
    (net (code "55") (name "Net-(U1-PC15)") (class "Default")
      (node (ref "C2") (pin "2") (pinfunction "2_2") (pintype "input"))
      (node (ref "U1") (pin "9") (pinfunction "PC15_9") (pintype "unspecified"))
      (node (ref "X1") (pin "1") (pinfunction "1_1") (pintype "input"))
    )
    (net (code "56") (name "Net-(U1-VCAP_1)") (class "Default")
      (node (ref "C3") (pin "2") (pinfunction "2_2") (pintype "input"))
      (node (ref "U1") (pin "49") (pinfunction "VCAP_1_49") (pintype "unspecified"))
    )
    (net (code "57") (name "Net-(U1-VCAP_2)") (class "Default")
      (node (ref "C4") (pin "1") (pinfunction "1_1") (pintype "input"))
      (node (ref "U1") (pin "73") (pinfunction "VCAP_2_73") (pintype "unspecified"))
    )
    (net (code "58") (name "Net-(U4-Pad3)") (class "Default")
      (node (ref "U4") (pin "3") (pinfunction "3_3") (pintype "unspecified"))
      (node (ref "U5") (pin "2") (pinfunction "2_2") (pintype "input"))
    )
    (net (code "59") (name "Net-(U6-ISEN)") (class "Default")
      (node (ref "U14") (pin "2") (pinfunction "2_2") (pintype "input"))
      (node (ref "U6") (pin "7") (pinfunction "ISEN_7") (pintype "unspecified"))
    )
    (net (code "60") (name "Net-(U6-OUT1)") (class "Default")
      (node (ref "U12") (pin "6") (pinfunction "6_6") (pintype "unspecified"))
      (node (ref "U6") (pin "6") (pinfunction "OUT1_6") (pintype "unspecified"))
    )
    (net (code "61") (name "Net-(U6-OUT2)") (class "Default")
      (node (ref "U12") (pin "1") (pinfunction "1_1") (pintype "unspecified"))
      (node (ref "U6") (pin "8") (pinfunction "OUT2_8") (pintype "unspecified"))
    )
    (net (code "62") (name "Net-(U7-ISEN)") (class "Default")
      (node (ref "U15") (pin "2") (pinfunction "2_2") (pintype "input"))
      (node (ref "U7") (pin "7") (pinfunction "ISEN_7") (pintype "unspecified"))
    )
    (net (code "63") (name "Net-(U7-OUT1)") (class "Default")
      (node (ref "U13") (pin "6") (pinfunction "6_6") (pintype "unspecified"))
      (node (ref "U7") (pin "6") (pinfunction "OUT1_6") (pintype "unspecified"))
    )
    (net (code "64") (name "Net-(U7-OUT2)") (class "Default")
      (node (ref "U13") (pin "1") (pinfunction "1_1") (pintype "unspecified"))
      (node (ref "U7") (pin "8") (pinfunction "OUT2_8") (pintype "unspecified"))
    )
    (net (code "65") (name "unconnected-(CN1-Pad4)") (class "Default")
      (node (ref "CN1") (pin "4") (pinfunction "4_4") (pintype "unspecified+no_connect"))
    )
    (net (code "66") (name "unconnected-(CN1-Pad5)") (class "Default")
      (node (ref "CN1") (pin "5") (pinfunction "5_5") (pintype "unspecified+no_connect"))
    )
    (net (code "67") (name "unconnected-(CN6-Pad5)") (class "Default")
      (node (ref "CN6") (pin "5") (pinfunction "5_5") (pintype "unspecified+no_connect"))
    )
    (net (code "68") (name "unconnected-(CN6-Pad6)") (class "Default")
      (node (ref "CN6") (pin "6") (pinfunction "6_6") (pintype "unspecified+no_connect"))
    )
    (net (code "69") (name "unconnected-(CN7-Pad5)") (class "Default")
      (node (ref "CN7") (pin "5") (pinfunction "5_5") (pintype "unspecified+no_connect"))
    )
    (net (code "70") (name "unconnected-(CN7-Pad6)") (class "Default")
      (node (ref "CN7") (pin "6") (pinfunction "6_6") (pintype "unspecified+no_connect"))
    )
    (net (code "71") (name "unconnected-(CN8-Pad5)") (class "Default")
      (node (ref "CN8") (pin "5") (pinfunction "5_5") (pintype "unspecified+no_connect"))
    )
    (net (code "72") (name "unconnected-(CN8-Pad6)") (class "Default")
      (node (ref "CN8") (pin "6") (pinfunction "6_6") (pintype "unspecified+no_connect"))
    )
    (net (code "73") (name "unconnected-(U1-PA2-Pad25)") (class "Default")
      (node (ref "U1") (pin "25") (pinfunction "PA2_25") (pintype "unspecified"))
    )
    (net (code "74") (name "unconnected-(U1-PA3-Pad26)") (class "Default")
      (node (ref "U1") (pin "26") (pinfunction "PA3_26") (pintype "unspecified"))
    )
    (net (code "75") (name "unconnected-(U1-PA4-Pad29)") (class "Default")
      (node (ref "U1") (pin "29") (pinfunction "PA4_29") (pintype "unspecified"))
    )
    (net (code "76") (name "unconnected-(U1-PA5-Pad30)") (class "Default")
      (node (ref "U1") (pin "30") (pinfunction "PA5_30") (pintype "unspecified"))
    )
    (net (code "77") (name "unconnected-(U1-PA8-Pad67)") (class "Default")
      (node (ref "U1") (pin "67") (pinfunction "PA8_67") (pintype "unspecified"))
    )
    (net (code "78") (name "unconnected-(U1-PA11-Pad70)") (class "Default")
      (node (ref "U1") (pin "70") (pinfunction "PA11_70") (pintype "unspecified"))
    )
    (net (code "79") (name "unconnected-(U1-PA12-Pad71)") (class "Default")
      (node (ref "U1") (pin "71") (pinfunction "PA12_71") (pintype "unspecified"))
    )
    (net (code "80") (name "unconnected-(U1-PA15-Pad77)") (class "Default")
      (node (ref "U1") (pin "77") (pinfunction "PA15_77") (pintype "unspecified"))
    )
    (net (code "81") (name "unconnected-(U1-PB0-Pad35)") (class "Default")
      (node (ref "U1") (pin "35") (pinfunction "PB0_35") (pintype "unspecified"))
    )
    (net (code "82") (name "unconnected-(U1-PB1-Pad36)") (class "Default")
      (node (ref "U1") (pin "36") (pinfunction "PB1_36") (pintype "unspecified"))
    )
    (net (code "83") (name "unconnected-(U1-PB8-Pad95)") (class "Default")
      (node (ref "U1") (pin "95") (pinfunction "PB8_95") (pintype "unspecified"))
    )
    (net (code "84") (name "unconnected-(U1-PB9-Pad96)") (class "Default")
      (node (ref "U1") (pin "96") (pinfunction "PB9_96") (pintype "unspecified"))
    )
    (net (code "85") (name "unconnected-(U1-PB15-Pad54)") (class "Default")
      (node (ref "U1") (pin "54") (pinfunction "PB15_54") (pintype "unspecified"))
    )
    (net (code "86") (name "unconnected-(U1-PC0-Pad15)") (class "Default")
      (node (ref "U1") (pin "15") (pinfunction "PC0_15") (pintype "unspecified"))
    )
    (net (code "87") (name "unconnected-(U1-PC1-Pad16)") (class "Default")
      (node (ref "U1") (pin "16") (pinfunction "PC1_16") (pintype "unspecified"))
    )
    (net (code "88") (name "unconnected-(U1-PC2-Pad17)") (class "Default")
      (node (ref "U1") (pin "17") (pinfunction "PC2_17") (pintype "unspecified"))
    )
    (net (code "89") (name "unconnected-(U1-PC3-Pad18)") (class "Default")
      (node (ref "U1") (pin "18") (pinfunction "PC3_18") (pintype "unspecified"))
    )
    (net (code "90") (name "unconnected-(U1-PC4-Pad33)") (class "Default")
      (node (ref "U1") (pin "33") (pinfunction "PC4_33") (pintype "unspecified"))
    )
    (net (code "91") (name "unconnected-(U1-PC5-Pad34)") (class "Default")
      (node (ref "U1") (pin "34") (pinfunction "PC5_34") (pintype "unspecified"))
    )
    (net (code "92") (name "unconnected-(U1-PC8-Pad65)") (class "Default")
      (node (ref "U1") (pin "65") (pinfunction "PC8_65") (pintype "unspecified"))
    )
    (net (code "93") (name "unconnected-(U1-PC9-Pad66)") (class "Default")
      (node (ref "U1") (pin "66") (pinfunction "PC9_66") (pintype "unspecified"))
    )
    (net (code "94") (name "unconnected-(U1-PC13-Pad7)") (class "Default")
      (node (ref "U1") (pin "7") (pinfunction "PC13_7") (pintype "unspecified"))
    )
    (net (code "95") (name "unconnected-(U1-PD0-Pad81)") (class "Default")
      (node (ref "U1") (pin "81") (pinfunction "PD0_81") (pintype "unspecified"))
    )
    (net (code "96") (name "unconnected-(U1-PD1-Pad82)") (class "Default")
      (node (ref "U1") (pin "82") (pinfunction "PD1_82") (pintype "unspecified"))
    )
    (net (code "97") (name "unconnected-(U1-PD3-Pad84)") (class "Default")
      (node (ref "U1") (pin "84") (pinfunction "PD3_84") (pintype "unspecified"))
    )
    (net (code "98") (name "unconnected-(U1-PD4-Pad85)") (class "Default")
      (node (ref "U1") (pin "85") (pinfunction "PD4_85") (pintype "unspecified"))
    )
    (net (code "99") (name "unconnected-(U1-PD8-Pad55)") (class "Default")
      (node (ref "U1") (pin "55") (pinfunction "PD8_55") (pintype "unspecified"))
    )
    (net (code "100") (name "unconnected-(U1-PE0-Pad97)") (class "Default")
      (node (ref "U1") (pin "97") (pinfunction "PE0_97") (pintype "unspecified"))
    )
    (net (code "101") (name "unconnected-(U1-PE2-Pad1)") (class "Default")
      (node (ref "U1") (pin "1") (pinfunction "PE2_1") (pintype "unspecified"))
    )
    (net (code "102") (name "unconnected-(U1-PE3-Pad2)") (class "Default")
      (node (ref "U1") (pin "2") (pinfunction "PE3_2") (pintype "unspecified"))
    )
    (net (code "103") (name "unconnected-(U1-PE4-Pad3)") (class "Default")
      (node (ref "U1") (pin "3") (pinfunction "PE4_3") (pintype "unspecified"))
    )
    (net (code "104") (name "unconnected-(U1-PE7-Pad38)") (class "Default")
      (node (ref "U1") (pin "38") (pinfunction "PE7_38") (pintype "unspecified"))
    )
    (net (code "105") (name "unconnected-(U1-PE8-Pad39)") (class "Default")
      (node (ref "U1") (pin "39") (pinfunction "PE8_39") (pintype "unspecified"))
    )
    (net (code "106") (name "unconnected-(U1-PE9-Pad40)") (class "Default")
      (node (ref "U1") (pin "40") (pinfunction "PE9_40") (pintype "unspecified"))
    )
    (net (code "107") (name "unconnected-(U1-PE10-Pad41)") (class "Default")
      (node (ref "U1") (pin "41") (pinfunction "PE10_41") (pintype "unspecified"))
    )
    (net (code "108") (name "unconnected-(U1-PE11-Pad42)") (class "Default")
      (node (ref "U1") (pin "42") (pinfunction "PE11_42") (pintype "unspecified"))
    )
    (net (code "109") (name "unconnected-(U1-PE12-Pad43)") (class "Default")
      (node (ref "U1") (pin "43") (pinfunction "PE12_43") (pintype "unspecified"))
    )
    (net (code "110") (name "unconnected-(U1-PE13-Pad44)") (class "Default")
      (node (ref "U1") (pin "44") (pinfunction "PE13_44") (pintype "unspecified"))
    )
    (net (code "111") (name "unconnected-(U1-PE14-Pad45)") (class "Default")
      (node (ref "U1") (pin "45") (pinfunction "PE14_45") (pintype "unspecified"))
    )
    (net (code "112") (name "unconnected-(U1-PE15-Pad46)") (class "Default")
      (node (ref "U1") (pin "46") (pinfunction "PE15_46") (pintype "unspecified"))
    )
    (net (code "113") (name "unconnected-(U4-Pad1)") (class "Default")
      (node (ref "U4") (pin "1") (pinfunction "1_1") (pintype "unspecified+no_connect"))
    )
    (net (code "114") (name "unconnected-(U12-Pad7)") (class "Default")
      (node (ref "U12") (pin "7") (pinfunction "7_7") (pintype "unspecified+no_connect"))
    )
    (net (code "115") (name "unconnected-(U12-Pad8)") (class "Default")
      (node (ref "U12") (pin "8") (pinfunction "8_8") (pintype "unspecified+no_connect"))
    )
    (net (code "116") (name "unconnected-(U13-Pad7)") (class "Default")
      (node (ref "U13") (pin "7") (pinfunction "7_7") (pintype "unspecified+no_connect"))
    )
    (net (code "117") (name "unconnected-(U13-Pad8)") (class "Default")
      (node (ref "U13") (pin "8") (pinfunction "8_8") (pintype "unspecified+no_connect"))
    )
  )
)
